# RP-LoRA_Mini_v2-1.net
KiCad netlist of a schematic drawn in EasyEDA Pro
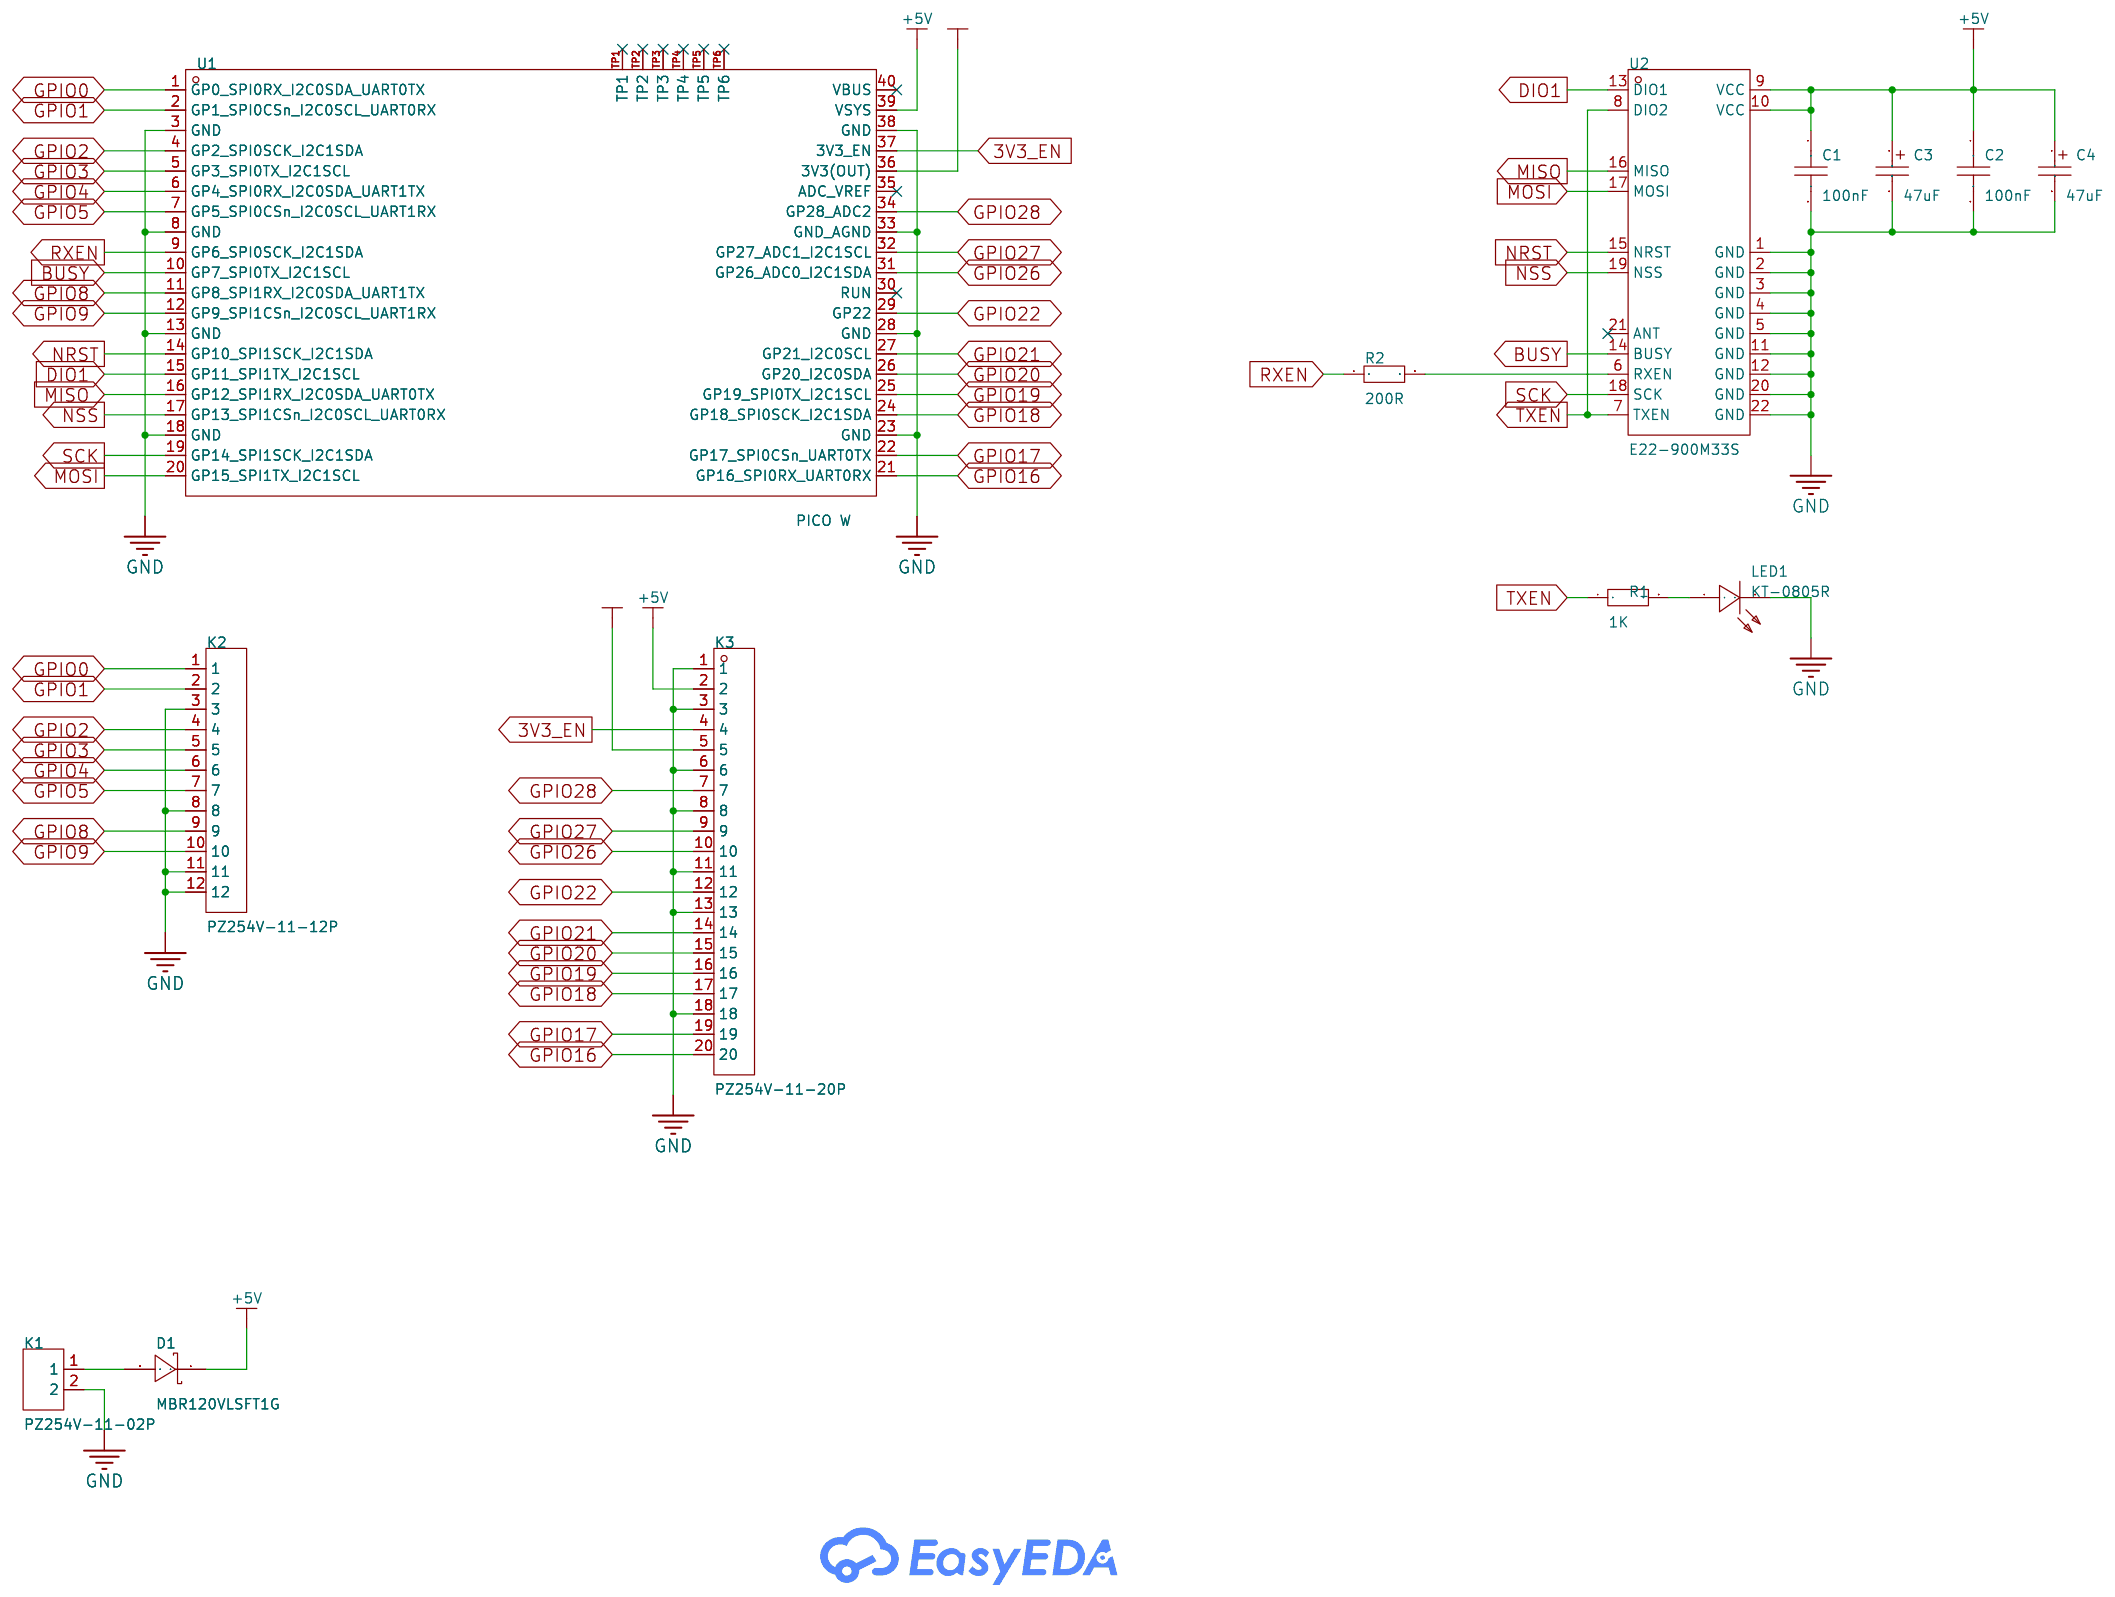
[diagram p0: schematic sheet]

(export (version "E")
  (design (tool "Eeschema 10.0.6"))
  (components
    (comp (ref "C1")
      (value "100nF")
      (footprint "easyedapro:C0603")
      (libsource (lib "easyedapro") (part "CAP"))
    )
    (comp (ref "C2")
      (value "100nF")
      (footprint "easyedapro:C0603")
      (libsource (lib "easyedapro") (part "CAP"))
    )
    (comp (ref "C3")
      (value "47uF")
      (footprint "easyedapro:CASE-B_3528")
      (fields
        (field (name "Manufacturer Part") "CA45-B-10V-47uF-K")
        (field (name "Manufacturer") "CEC(振华新云)")
      )
      (libsource (lib "easyedapro") (part "CA45-B-10V-47UF-K"))
    )
    (comp (ref "C4")
      (value "47uF")
      (footprint "easyedapro:CASE-B_3528")
      (fields
        (field (name "Manufacturer Part") "CA45-B-10V-47uF-K")
        (field (name "Manufacturer") "CEC(振华新云)")
      )
      (libsource (lib "easyedapro") (part "CA45-B-10V-47UF-K"))
    )
    (comp (ref "D1")
      (value "MBR120VLSFT1G")
      (footprint "easyedapro:SOD-123F_L2.8-W1.8-LS3.7-RD")
      (fields (field (name "Manufacturer") "onsemi(安森美)"))
      (libsource (lib "easyedapro") (part "MBR120VLSFT1G"))
    )
    (comp (ref "K1")
      (value "PZ254V-11-02P")
      (footprint "easyedapro:HDR-TH_2P-P2.54-V-M")
      (fields (field (name "Manufacturer") "XFCN(兴飞)"))
      (libsource (lib "easyedapro") (part "PZ254V-11-02P"))
    )
    (comp (ref "K2")
      (value "PZ254V-11-12P")
      (footprint "easyedapro:HDR-TH_12P-P2.54-V-M")
      (fields (field (name "Manufacturer") "XFCN(兴飞)"))
      (libsource (lib "easyedapro") (part "PZ254V-11-12P"))
    )
    (comp (ref "K3")
      (value "PZ254V-11-20P")
      (footprint "easyedapro:HDR-TH_20P-P2.54-V-M-4")
      (fields (field (name "Manufacturer") "XFCN(兴飞)"))
      (libsource (lib "easyedapro") (part "PZ254V-11-20P"))
    )
    (comp (ref "LED1")
      (value "KT-0805R")
      (footprint "easyedapro:LED0805-R-RD")
      (fields (field (name "Manufacturer") "KENTO"))
      (libsource (lib "easyedapro") (part "E6C0805UR"))
    )
    (comp (ref "R1") (value "1K") (footprint "easyedapro:R0603") (libsource (lib "easyedapro") (part "Res")))
    (comp (ref "R2")
      (value "200R")
      (footprint "easyedapro:R0603")
      (libsource (lib "easyedapro") (part "Res"))
    )
    (comp (ref "U1")
      (value "PICO W")
      (footprint "easyedapro:COMM-SMD_L51.0-W21.0-P2.54_PICOW")
      (fields (field (name "Manufacturer") "Raspberry Pi(树莓派)"))
      (libsource (lib "easyedapro") (part "PICO W"))
    )
    (comp (ref "U2")
      (value "E22-900M33S")
      (footprint "easyedapro:COMM-SMD_22P-P2.54-L38.5-W24.0_E22-400M33S")
      (fields (field (name "Manufacturer") "EBYTE(亿佰特)"))
      (libsource (lib "easyedapro") (part "E22-900M33S"))
    )
  )
  (nets
    (net (code "1") (name "+3V3") (class "Default")
      (node (ref "K3") (pin "5") (pinfunction "5_5") (pintype "unspecified"))
      (node (ref "U1") (pin "36") (pinfunction "3V3(OUT)_36") (pintype "unspecified"))
    )
    (net (code "2") (name "+5V") (class "Default")
      (node (ref "C1") (pin "1") (pinfunction "1_1") (pintype "input"))
      (node (ref "C2") (pin "1") (pinfunction "1_1") (pintype "input"))
      (node (ref "C3") (pin "1") (pinfunction "1_1") (pintype "input"))
      (node (ref "C4") (pin "1") (pinfunction "1_1") (pintype "input"))
      (node (ref "D1") (pin "1") (pinfunction "K_1") (pintype "unspecified"))
      (node (ref "K3") (pin "2") (pinfunction "2_2") (pintype "unspecified"))
      (node (ref "U1") (pin "39") (pinfunction "VSYS_39") (pintype "unspecified"))
      (node (ref "U2") (pin "10") (pinfunction "VCC_10") (pintype "unspecified"))
      (node (ref "U2") (pin "9") (pinfunction "VCC_9") (pintype "unspecified"))
    )
    (net (code "3") (name "3V3_EN") (class "Default")
      (node (ref "K3") (pin "4") (pinfunction "4_4") (pintype "unspecified"))
      (node (ref "U1") (pin "37") (pinfunction "3V3_EN_37") (pintype "unspecified"))
    )
    (net (code "4") (name "BUSY") (class "Default")
      (node (ref "U1") (pin "10") (pinfunction "GP7_SPI0TX_I2C1SCL_10") (pintype "unspecified"))
      (node (ref "U2") (pin "14") (pinfunction "BUSY_14") (pintype "unspecified"))
    )
    (net (code "5") (name "DIO1") (class "Default")
      (node (ref "U1") (pin "15") (pinfunction "GP11_SPI1TX_I2C1SCL_15") (pintype "unspecified"))
      (node (ref "U2") (pin "13") (pinfunction "DIO1_13") (pintype "unspecified"))
    )
    (net (code "6") (name "GND") (class "Default")
      (node (ref "C1") (pin "2") (pinfunction "2_2") (pintype "input"))
      (node (ref "C2") (pin "2") (pinfunction "2_2") (pintype "input"))
      (node (ref "C3") (pin "2") (pinfunction "2_2") (pintype "input"))
      (node (ref "C4") (pin "2") (pinfunction "2_2") (pintype "input"))
      (node (ref "K1") (pin "2") (pinfunction "2_2") (pintype "unspecified"))
      (node (ref "K2") (pin "11") (pinfunction "11_11") (pintype "unspecified"))
      (node (ref "K2") (pin "12") (pinfunction "12_12") (pintype "unspecified"))
      (node (ref "K2") (pin "3") (pinfunction "3_3") (pintype "unspecified"))
      (node (ref "K2") (pin "8") (pinfunction "8_8") (pintype "unspecified"))
      (node (ref "K3") (pin "1") (pinfunction "1_1") (pintype "unspecified"))
      (node (ref "K3") (pin "11") (pinfunction "11_11") (pintype "unspecified"))
      (node (ref "K3") (pin "13") (pinfunction "13_13") (pintype "unspecified"))
      (node (ref "K3") (pin "18") (pinfunction "18_18") (pintype "unspecified"))
      (node (ref "K3") (pin "3") (pinfunction "3_3") (pintype "unspecified"))
      (node (ref "K3") (pin "6") (pinfunction "6_6") (pintype "unspecified"))
      (node (ref "K3") (pin "8") (pinfunction "8_8") (pintype "unspecified"))
      (node (ref "LED1") (pin "2") (pinfunction "K_2") (pintype "unspecified"))
      (node (ref "U1") (pin "13") (pinfunction "GND_13") (pintype "unspecified"))
      (node (ref "U1") (pin "18") (pinfunction "GND_18") (pintype "unspecified"))
      (node (ref "U1") (pin "23") (pinfunction "GND_23") (pintype "unspecified"))
      (node (ref "U1") (pin "28") (pinfunction "GND_28") (pintype "unspecified"))
      (node (ref "U1") (pin "3") (pinfunction "GND_3") (pintype "unspecified"))
      (node (ref "U1") (pin "33") (pinfunction "GND_AGND_33") (pintype "unspecified"))
      (node (ref "U1") (pin "38") (pinfunction "GND_38") (pintype "unspecified"))
      (node (ref "U1") (pin "8") (pinfunction "GND_8") (pintype "unspecified"))
      (node (ref "U2") (pin "1") (pinfunction "GND_1") (pintype "unspecified"))
      (node (ref "U2") (pin "11") (pinfunction "GND_11") (pintype "unspecified"))
      (node (ref "U2") (pin "12") (pinfunction "GND_12") (pintype "unspecified"))
      (node (ref "U2") (pin "2") (pinfunction "GND_2") (pintype "unspecified"))
      (node (ref "U2") (pin "20") (pinfunction "GND_20") (pintype "unspecified"))
      (node (ref "U2") (pin "22") (pinfunction "GND_22") (pintype "unspecified"))
      (node (ref "U2") (pin "3") (pinfunction "GND_3") (pintype "unspecified"))
      (node (ref "U2") (pin "4") (pinfunction "GND_4") (pintype "unspecified"))
      (node (ref "U2") (pin "5") (pinfunction "GND_5") (pintype "unspecified"))
    )
    (net (code "7") (name "GPIO0") (class "Default")
      (node (ref "K2") (pin "1") (pinfunction "1_1") (pintype "unspecified"))
      (node (ref "U1") (pin "1") (pinfunction "GP0_SPI0RX_I2C0SDA_UART0TX_1") (pintype "unspecified"))
    )
    (net (code "8") (name "GPIO1") (class "Default")
      (node (ref "K2") (pin "2") (pinfunction "2_2") (pintype "unspecified"))
      (node (ref "U1") (pin "2") (pinfunction "GP1_SPI0CSn_I2C0SCL_UART0RX_2") (pintype "unspecified"))
    )
    (net (code "9") (name "GPIO2") (class "Default")
      (node (ref "K2") (pin "4") (pinfunction "4_4") (pintype "unspecified"))
      (node (ref "U1") (pin "4") (pinfunction "GP2_SPI0SCK_I2C1SDA_4") (pintype "unspecified"))
    )
    (net (code "10") (name "GPIO3") (class "Default")
      (node (ref "K2") (pin "5") (pinfunction "5_5") (pintype "unspecified"))
      (node (ref "U1") (pin "5") (pinfunction "GP3_SPI0TX_I2C1SCL_5") (pintype "unspecified"))
    )
    (net (code "11") (name "GPIO4") (class "Default")
      (node (ref "K2") (pin "6") (pinfunction "6_6") (pintype "unspecified"))
      (node (ref "U1") (pin "6") (pinfunction "GP4_SPI0RX_I2C0SDA_UART1TX_6") (pintype "unspecified"))
    )
    (net (code "12") (name "GPIO5") (class "Default")
      (node (ref "K2") (pin "7") (pinfunction "7_7") (pintype "unspecified"))
      (node (ref "U1") (pin "7") (pinfunction "GP5_SPI0CSn_I2C0SCL_UART1RX_7") (pintype "unspecified"))
    )
    (net (code "13") (name "GPIO8") (class "Default")
      (node (ref "K2") (pin "9") (pinfunction "9_9") (pintype "unspecified"))
      (node (ref "U1") (pin "11") (pinfunction "GP8_SPI1RX_I2C0SDA_UART1TX_11") (pintype "unspecified"))
    )
    (net (code "14") (name "GPIO9") (class "Default")
      (node (ref "K2") (pin "10") (pinfunction "10_10") (pintype "unspecified"))
      (node (ref "U1") (pin "12") (pinfunction "GP9_SPI1CSn_I2C0SCL_UART1RX_12") (pintype "unspecified"))
    )
    (net (code "15") (name "GPIO16") (class "Default")
      (node (ref "K3") (pin "20") (pinfunction "20_20") (pintype "unspecified"))
      (node (ref "U1") (pin "21") (pinfunction "GP16_SPI0RX_UART0RX_21") (pintype "unspecified"))
    )
    (net (code "16") (name "GPIO17") (class "Default")
      (node (ref "K3") (pin "19") (pinfunction "19_19") (pintype "unspecified"))
      (node (ref "U1") (pin "22") (pinfunction "GP17_SPI0CSn_UART0TX_22") (pintype "unspecified"))
    )
    (net (code "17") (name "GPIO18") (class "Default")
      (node (ref "K3") (pin "17") (pinfunction "17_17") (pintype "unspecified"))
      (node (ref "U1") (pin "24") (pinfunction "GP18_SPI0SCK_I2C1SDA_24") (pintype "unspecified"))
    )
    (net (code "18") (name "GPIO19") (class "Default")
      (node (ref "K3") (pin "16") (pinfunction "16_16") (pintype "unspecified"))
      (node (ref "U1") (pin "25") (pinfunction "GP19_SPI0TX_I2C1SCL_25") (pintype "unspecified"))
    )
    (net (code "19") (name "GPIO20") (class "Default")
      (node (ref "K3") (pin "15") (pinfunction "15_15") (pintype "unspecified"))
      (node (ref "U1") (pin "26") (pinfunction "GP20_I2C0SDA_26") (pintype "unspecified"))
    )
    (net (code "20") (name "GPIO21") (class "Default")
      (node (ref "K3") (pin "14") (pinfunction "14_14") (pintype "unspecified"))
      (node (ref "U1") (pin "27") (pinfunction "GP21_I2C0SCL_27") (pintype "unspecified"))
    )
    (net (code "21") (name "GPIO22") (class "Default")
      (node (ref "K3") (pin "12") (pinfunction "12_12") (pintype "unspecified"))
      (node (ref "U1") (pin "29") (pinfunction "GP22_29") (pintype "unspecified"))
    )
    (net (code "22") (name "GPIO26") (class "Default")
      (node (ref "K3") (pin "10") (pinfunction "10_10") (pintype "unspecified"))
      (node (ref "U1") (pin "31") (pinfunction "GP26_ADC0_I2C1SDA_31") (pintype "unspecified"))
    )
    (net (code "23") (name "GPIO27") (class "Default")
      (node (ref "K3") (pin "9") (pinfunction "9_9") (pintype "unspecified"))
      (node (ref "U1") (pin "32") (pinfunction "GP27_ADC1_I2C1SCL_32") (pintype "unspecified"))
    )
    (net (code "24") (name "GPIO28") (class "Default")
      (node (ref "K3") (pin "7") (pinfunction "7_7") (pintype "unspecified"))
      (node (ref "U1") (pin "34") (pinfunction "GP28_ADC2_34") (pintype "unspecified"))
    )
    (net (code "25") (name "MISO") (class "Default")
      (node (ref "U1") (pin "16") (pinfunction "GP12_SPI1RX_I2C0SDA_UART0TX_16") (pintype "unspecified"))
      (node (ref "U2") (pin "16") (pinfunction "MISO_16") (pintype "unspecified"))
    )
    (net (code "26") (name "MOSI") (class "Default")
      (node (ref "U1") (pin "20") (pinfunction "GP15_SPI1TX_I2C1SCL_20") (pintype "unspecified"))
      (node (ref "U2") (pin "17") (pinfunction "MOSI_17") (pintype "unspecified"))
    )
    (net (code "27") (name "NRST") (class "Default")
      (node (ref "U1") (pin "14") (pinfunction "GP10_SPI1SCK_I2C1SDA_14") (pintype "unspecified"))
      (node (ref "U2") (pin "15") (pinfunction "NRST_15") (pintype "unspecified"))
    )
    (net (code "28") (name "NSS") (class "Default")
      (node (ref "U1") (pin "17") (pinfunction "GP13_SPI1CSn_I2C0SCL_UART0RX_17") (pintype "unspecified"))
      (node (ref "U2") (pin "19") (pinfunction "NSS_19") (pintype "unspecified"))
    )
    (net (code "29") (name "Net-(D1-A)") (class "Default")
      (node (ref "D1") (pin "2") (pinfunction "A_2") (pintype "unspecified"))
      (node (ref "K1") (pin "1") (pinfunction "1_1") (pintype "unspecified"))
    )
    (net (code "30") (name "Net-(LED1-A)") (class "Default")
      (node (ref "LED1") (pin "1") (pinfunction "A_1") (pintype "unspecified"))
      (node (ref "R1") (pin "2") (pinfunction "2_2") (pintype "input"))
    )
    (net (code "31") (name "Net-(U2-RXEN)") (class "Default")
      (node (ref "R2") (pin "2") (pinfunction "2_2") (pintype "input"))
      (node (ref "U2") (pin "6") (pinfunction "RXEN_6") (pintype "unspecified"))
    )
    (net (code "32") (name "RXEN") (class "Default")
      (node (ref "R2") (pin "1") (pinfunction "1_1") (pintype "input"))
      (node (ref "U1") (pin "9") (pinfunction "GP6_SPI0SCK_I2C1SDA_9") (pintype "unspecified"))
    )
    (net (code "33") (name "SCK") (class "Default")
      (node (ref "U1") (pin "19") (pinfunction "GP14_SPI1SCK_I2C1SDA_19") (pintype "unspecified"))
      (node (ref "U2") (pin "18") (pinfunction "SCK_18") (pintype "unspecified"))
    )
    (net (code "34") (name "TXEN") (class "Default")
      (node (ref "R1") (pin "1") (pinfunction "1_1") (pintype "input"))
      (node (ref "U2") (pin "7") (pinfunction "TXEN_7") (pintype "unspecified"))
      (node (ref "U2") (pin "8") (pinfunction "DIO2_8") (pintype "unspecified"))
    )
    (net (code "35") (name "unconnected-(U1-ADC_VREF-Pad35)") (class "Default")
      (node (ref "U1") (pin "35") (pinfunction "ADC_VREF_35") (pintype "unspecified+no_connect"))
    )
    (net (code "36") (name "unconnected-(U1-PadTP1)") (class "Default")
      (node (ref "U1") (pin "TP1") (pinfunction "TP1_TP1") (pintype "unspecified+no_connect"))
    )
    (net (code "37") (name "unconnected-(U1-PadTP2)") (class "Default")
      (node (ref "U1") (pin "TP2") (pinfunction "TP2_TP2") (pintype "unspecified+no_connect"))
    )
    (net (code "38") (name "unconnected-(U1-PadTP3)") (class "Default")
      (node (ref "U1") (pin "TP3") (pinfunction "TP3_TP3") (pintype "unspecified+no_connect"))
    )
    (net (code "39") (name "unconnected-(U1-PadTP4)") (class "Default")
      (node (ref "U1") (pin "TP4") (pinfunction "TP4_TP4") (pintype "unspecified+no_connect"))
    )
    (net (code "40") (name "unconnected-(U1-PadTP5)") (class "Default")
      (node (ref "U1") (pin "TP5") (pinfunction "TP5_TP5") (pintype "unspecified+no_connect"))
    )
    (net (code "41") (name "unconnected-(U1-PadTP6)") (class "Default")
      (node (ref "U1") (pin "TP6") (pinfunction "TP6_TP6") (pintype "unspecified+no_connect"))
    )
    (net (code "42") (name "unconnected-(U1-RUN-Pad30)") (class "Default")
      (node (ref "U1") (pin "30") (pinfunction "RUN_30") (pintype "unspecified+no_connect"))
    )
    (net (code "43") (name "unconnected-(U1-VBUS-Pad40)") (class "Default")
      (node (ref "U1") (pin "40") (pinfunction "VBUS_40") (pintype "unspecified+no_connect"))
    )
    (net (code "44") (name "unconnected-(U2-ANT-Pad21)") (class "Default")
      (node (ref "U2") (pin "21") (pinfunction "ANT_21") (pintype "unspecified+no_connect"))
    )
  )
)
